# flyback.net
KiCad netlist of a schematic drawn in Altium Designer
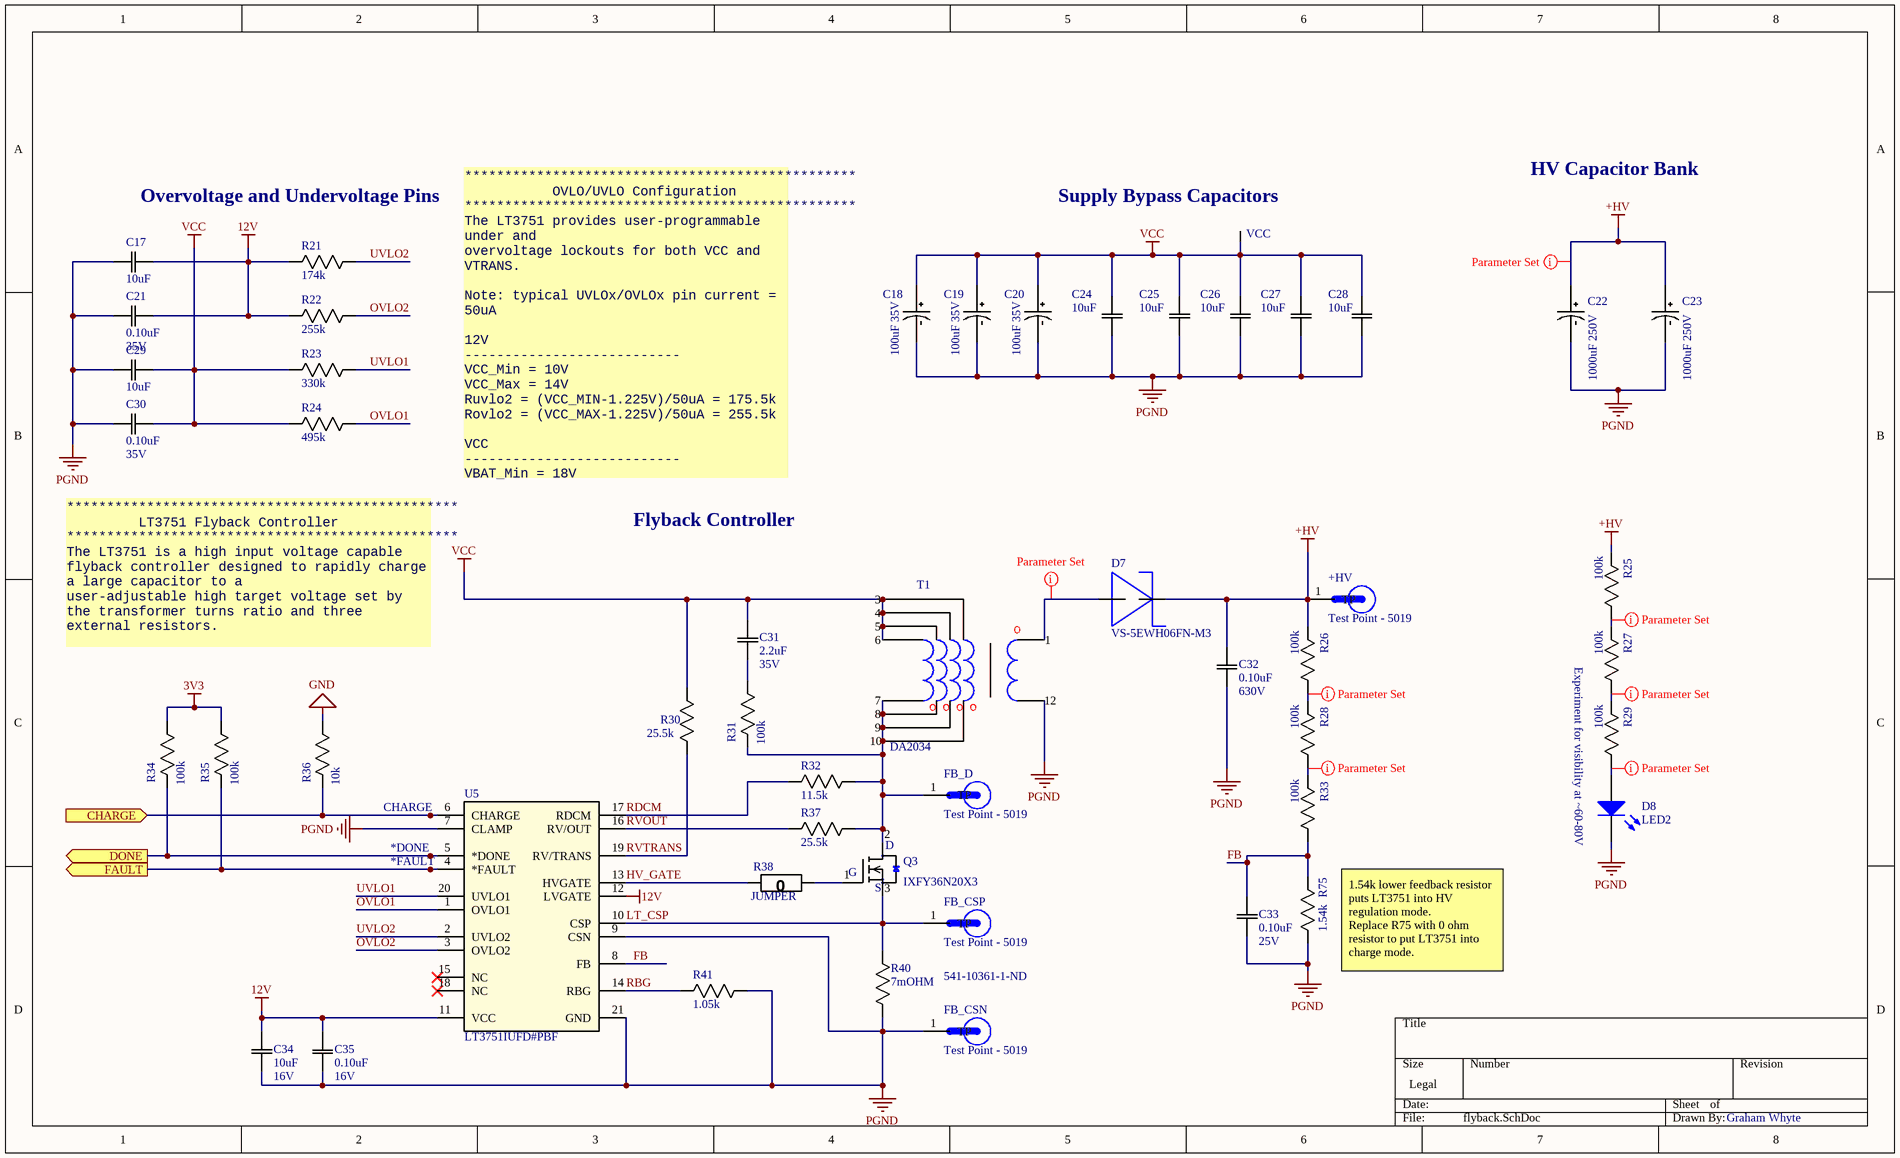
[diagram p0: flyback.SchDoc]

(export (version "E")
  (design (tool "Eeschema 10.0.6"))
  (components
    (comp (ref "*DONE")
      (value "Test Point (Via)")
      (footprint "TP")
      (libsource (lib "IC_Library") (part "Test Point (Via)"))
    )
    (comp (ref "*FAULT")
      (value "Test Point (Via)")
      (footprint "TP")
      (libsource (lib "IC_Library") (part "Test Point (Via)"))
    )
    (comp (ref "+HV")
      (value "Test Point - 5019")
      (footprint "TP380X203")
      (description "PC Test Point, Miniature Phosphor Bronze, Silver Plating Surface Mount Mounting Type")
      (fields (field (name "MP") "5019") (field (name "MF") "Keystone Electronics"))
      (libsource (lib "IC_Library") (part "Test Point - 5019"))
    )
    (comp (ref "C17")
      (value "10uF")
      (footprint "0805")
      (description "CAP CER 10UF 35V X7R 0805")
      (fields (field (name "TOLERANCE") "10%") (field (name "PART NUMBER") "CAP 10uF 35V"))
      (libsource (lib "capacitor_library") (part "CAP 10uF 35V"))
    )
    (comp (ref "C18")
      (value "100uF 35V")
      (footprint "CAP POL ALU 6.3x5.8")
      (description "CAP ALUM 100UF 35V SMD")
      (fields (field (name "TOLERANCE") "20%") (field (name "PART NUMBER") "CAP POL 100uF SMD"))
      (libsource (lib "capacitor_library") (part "CAP POL 100uF SMD"))
    )
    (comp (ref "C19")
      (value "100uF 35V")
      (footprint "CAP POL ALU 6.3x5.8")
      (description "CAP ALUM 100UF 35V SMD")
      (fields (field (name "TOLERANCE") "20%") (field (name "PART NUMBER") "CAP POL 100uF SMD"))
      (libsource (lib "capacitor_library") (part "CAP POL 100uF SMD"))
    )
    (comp (ref "C20")
      (value "100uF 35V")
      (footprint "CAP POL ALU 6.3x5.8")
      (description "CAP ALUM 100UF 35V SMD")
      (fields (field (name "TOLERANCE") "20%") (field (name "PART NUMBER") "CAP POL 100uF SMD"))
      (libsource (lib "capacitor_library") (part "CAP POL 100uF SMD"))
    )
    (comp (ref "C21")
      (value "0.10uF")
      (footprint "0805")
      (description "CAP CER 0.10UF 35V X7R 0805")
      (fields
        (field (name "TOLERANCE") "10%")
        (field (name "RATING") "35V")
        (field (name "PART NUMBER") "CAP 0.10uF 35V")
      )
      (libsource (lib "capacitor_library") (part "CAP 0.10uF 35V"))
    )
    (comp (ref "C22")
      (value "1000uF 250V")
      (footprint "RADIAL, CAN - THRU 25.4mm")
      (description "United Chemi-Con\r\nESMQ251VSN102MQ45S")
      (fields
        (field (name "MANUFACTURER") "United Chemi-Con")
        (field (name "MANUFACTURER PART NUMBER") "ESMQ251VSN102MQ45S")
      )
      (libsource (lib "capacitor_library") (part "CAP POL 1000uF"))
    )
    (comp (ref "C23")
      (value "1000uF 250V")
      (footprint "RADIAL, CAN - THRU 25.4mm")
      (description "United Chemi-Con\r\nESMQ251VSN102MQ45S")
      (fields
        (field (name "MANUFACTURER") "United Chemi-Con")
        (field (name "MANUFACTURER PART NUMBER") "ESMQ251VSN102MQ45S")
      )
      (libsource (lib "capacitor_library") (part "CAP POL 1000uF"))
    )
    (comp (ref "C24")
      (value "10uF")
      (footprint "0805")
      (description "CAP CER 10UF 35V X7R 0805")
      (fields (field (name "TOLERANCE") "10%") (field (name "PART NUMBER") "CAP 10uF 35V"))
      (libsource (lib "capacitor_library") (part "CAP 10uF 35V"))
    )
    (comp (ref "C25")
      (value "10uF")
      (footprint "0805")
      (description "CAP CER 10UF 35V X7R 0805")
      (fields (field (name "TOLERANCE") "10%") (field (name "PART NUMBER") "CAP 10uF 35V"))
      (libsource (lib "capacitor_library") (part "CAP 10uF 35V"))
    )
    (comp (ref "C26")
      (value "10uF")
      (footprint "0805")
      (description "CAP CER 10UF 35V X7R 0805")
      (fields (field (name "TOLERANCE") "10%") (field (name "PART NUMBER") "CAP 10uF 35V"))
      (libsource (lib "capacitor_library") (part "CAP 10uF 35V"))
    )
    (comp (ref "C27")
      (value "10uF")
      (footprint "0805")
      (description "CAP CER 10UF 35V X7R 0805")
      (fields (field (name "TOLERANCE") "10%") (field (name "PART NUMBER") "CAP 10uF 35V"))
      (libsource (lib "capacitor_library") (part "CAP 10uF 35V"))
    )
    (comp (ref "C28")
      (value "10uF")
      (footprint "0805")
      (description "CAP CER 10UF 35V X7R 0805")
      (fields (field (name "TOLERANCE") "10%") (field (name "PART NUMBER") "CAP 10uF 35V"))
      (libsource (lib "capacitor_library") (part "CAP 10uF 35V"))
    )
    (comp (ref "C29")
      (value "10uF")
      (footprint "0805")
      (description "CAP CER 10UF 35V X7R 0805")
      (fields (field (name "TOLERANCE") "10%") (field (name "PART NUMBER") "CAP 10uF 35V"))
      (libsource (lib "capacitor_library") (part "CAP 10uF 35V"))
    )
    (comp (ref "C30")
      (value "0.10uF")
      (footprint "0805")
      (description "CAP CER 0.10UF 35V X7R 0805")
      (fields
        (field (name "TOLERANCE") "10%")
        (field (name "RATING") "35V")
        (field (name "PART NUMBER") "CAP 0.10uF 35V")
      )
      (libsource (lib "capacitor_library") (part "CAP 0.10uF 35V"))
    )
    (comp (ref "C31")
      (value "2.2uF")
      (footprint "0603")
      (description "CAP CER 2.2UF 35V X7R 0603/0805")
      (fields
        (field (name "TOLERANCE") "10%")
        (field (name "RATING") "35V")
        (field (name "PART NUMBER") "CAP 2.2uF 35V")
      )
      (libsource (lib "capacitor_library") (part "CAP 2.2uF 35V"))
    )
    (comp (ref "C32")
      (value "0.10uF")
      (footprint "1210")
      (description "CAP CER 0.1uF 630V X7R 1210")
      (fields
        (field (name "TOLERANCE") "10%")
        (field (name "RATING") "630V")
        (field (name "PART NUMBER") "CAP 0.10uF 630V")
      )
      (libsource (lib "capacitor_library") (part "CAP 0.10uF 630V"))
    )
    (comp (ref "C33")
      (value "0.10uF")
      (footprint "0805")
      (description "CAP CER 0.10UF 25V X7R 0805")
      (fields
        (field (name "TOLERANCE") "10%")
        (field (name "RATING") "25V")
        (field (name "PART NUMBER") "CAP 0.10uF 25V")
      )
      (libsource (lib "capacitor_library") (part "CAP 0.10uF 25V"))
    )
    (comp (ref "C34")
      (value "10uF")
      (footprint "0603")
      (description "CAP CER 10UF 16V X5R 0603/0805")
      (fields
        (field (name "TOLERANCE") "10%")
        (field (name "RATING") "16V")
        (field (name "PART NUMBER") "CAP 10uF 16V")
      )
      (libsource (lib "capacitor_library") (part "CAP 10uF 16V"))
    )
    (comp (ref "C35")
      (value "0.10uF")
      (footprint "0603")
      (description "CAP CER 0.10UF 16V X5R 0603")
      (fields
        (field (name "TOLERANCE") "10%")
        (field (name "RATING") "16V")
        (field (name "PART NUMBER") "CAP 0.10uF 16V")
      )
      (libsource (lib "capacitor_library") (part "CAP 0.10uF 16V"))
    )
    (comp (ref "CHARGE")
      (value "Test Point (Via)")
      (footprint "TP")
      (libsource (lib "IC_Library") (part "Test Point (Via)"))
    )
    (comp (ref "D7")
      (value "VS-5EWH06FN-M3")
      (footprint "DPAK (TO-252)")
      (description "Diode Switching 600V 5A DPAK")
      (fields (field (name "MF") "Vishay Diodes"))
      (libsource (lib "Diode_Library") (part "VS-5EWH06FN-M3"))
    )
    (comp (ref "D8")
      (value "LED2")
      (footprint "3.2X1.6X1.1")
      (description "Typical RED, GREEN, YELLOW, AMBER GaAs LED")
      (fields (field (name "PART NUMBER") "LED GREEN SMD"))
      (libsource (lib "Diode_Library") (part "LED GREEN SMD"))
    )
    (comp (ref "FB_CSN")
      (value "Test Point - 5019")
      (footprint "TP380X203")
      (description "PC Test Point, Miniature Phosphor Bronze, Silver Plating Surface Mount Mounting Type")
      (fields (field (name "MP") "5019") (field (name "MF") "Keystone Electronics"))
      (libsource (lib "IC_Library") (part "Test Point - 5019"))
    )
    (comp (ref "FB_CSP")
      (value "Test Point - 5019")
      (footprint "TP380X203")
      (description "PC Test Point, Miniature Phosphor Bronze, Silver Plating Surface Mount Mounting Type")
      (fields (field (name "MP") "5019") (field (name "MF") "Keystone Electronics"))
      (libsource (lib "IC_Library") (part "Test Point - 5019"))
    )
    (comp (ref "FB_D")
      (value "Test Point - 5019")
      (footprint "TP380X203")
      (description "PC Test Point, Miniature Phosphor Bronze, Silver Plating Surface Mount Mounting Type")
      (fields (field (name "MP") "5019") (field (name "MF") "Keystone Electronics"))
      (libsource (lib "IC_Library") (part "Test Point - 5019"))
    )
    (comp (ref "Q3")
      (value "IXFY36N20X3")
      (footprint "DPAK (TO-252)")
      (description "N-Channel 200 V 36A (Tc) 176W (Tc) Surface Mount TO-252AA")
      (fields (field (name "PART NUMBER") "MOSFET N-CH IXFY36N20X3"))
      (libsource (lib "Transistor_Library") (part "MOSFET N-CH IXFY36N20X3"))
    )
    (comp (ref "R21")
      (value "174k")
      (footprint "0603")
      (description "RES SMD 174K OHM 1% 1/8W 0603")
      (fields
        (field (name "MANUFACTURER") "Yageo")
        (field (name "MANUFACTURER PART NUMBER") "RC0805FR-07174KL")
      )
      (libsource (lib "Resistor_Library") (part "RES 174k 1/8W"))
    )
    (comp (ref "R22")
      (value "255k")
      (footprint "0603")
      (description "RES 255k 1/8W - 1% 0603")
      (fields (field (name "PART NUMBER") "RES 255k 1/8W - 1%"))
      (libsource (lib "Resistor_Library") (part "RES 255k 1/8W - 1%"))
    )
    (comp (ref "R23")
      (value "330k")
      (footprint "0603")
      (description "RES SMD 274K OHM 1% 1/8W 0603")
      (fields (field (name "PART NUMBER") "RES 330k 1/8W - 1%"))
      (libsource (lib "Resistor_Library") (part "RES 330k 1/8W - 1%"))
    )
    (comp (ref "R24")
      (value "495k")
      (footprint "0603")
      (description "RES SMD 495K OHM 1% 1/8W 0603")
      (fields
        (field (name "MANUFACTURER") "Yageo")
        (field (name "MANUFACTURER PART NUMBER") "RC0805FR-07499KL")
      )
      (libsource (lib "Resistor_Library") (part "RES 495k 1/8W"))
    )
    (comp (ref "R25")
      (value "100k")
      (footprint "0603")
      (description "RES SMD 100K OHM 5% 1/8W 0603")
      (fields (field (name "TOLERANCE") "5%") (field (name "PART NUMBER") "RES 100k 1/8W - 5%"))
      (libsource (lib "") (part "RES 100k 1/8W 5%_1"))
    )
    (comp (ref "R26")
      (value "100k")
      (footprint "0603")
      (description "RES SMD 100K OHM 1% 1/8W 0603")
      (fields (field (name "TOLERANCE") "1%") (field (name "PART NUMBER") "RES 100k 1/8W - 1%"))
      (libsource (lib "") (part "RES 100k 1/8W 1%_1"))
    )
    (comp (ref "R27")
      (value "100k")
      (footprint "0603")
      (description "RES SMD 100K OHM 5% 1/8W 0603")
      (fields (field (name "TOLERANCE") "5%") (field (name "PART NUMBER") "RES 100k 1/8W - 5%"))
      (libsource (lib "Resistor_Library") (part "RES 100k 1/8W 5%"))
    )
    (comp (ref "R28")
      (value "100k")
      (footprint "0603")
      (description "RES SMD 100K OHM 1% 1/8W 0603")
      (fields (field (name "TOLERANCE") "1%") (field (name "PART NUMBER") "RES 100k 1/8W - 1%"))
      (libsource (lib "Resistor_Library") (part "RES 100k 1/8W 1%"))
    )
    (comp (ref "R29")
      (value "100k")
      (footprint "0603")
      (description "RES SMD 100K OHM 5% 1/8W 0603")
      (fields (field (name "TOLERANCE") "5%") (field (name "PART NUMBER") "RES 100k 1/8W - 5%"))
      (libsource (lib "Resistor_Library") (part "RES 100k 1/8W 5%"))
    )
    (comp (ref "R30")
      (value "25.5k")
      (footprint "0603")
      (description "RES SMD 25.5K OHM 0.1% 1/8W 0603")
      (fields
        (field (name "MANUFACTURER") "Panasonic")
        (field (name "MANUFACTURER PART NUMBER") "ERA-6AEB2552V")
      )
      (libsource (lib "Resistor_Library") (part "RES 25.5k 1/8W"))
    )
    (comp (ref "R31")
      (value "100k")
      (footprint "0603")
      (description "RES SMD 100K OHM 1% 1/8W 0603")
      (fields (field (name "TOLERANCE") "1%") (field (name "PART NUMBER") "RES 100k 1/8W - 1%"))
      (libsource (lib "") (part "RES 100k 1/8W 1%_1"))
    )
    (comp (ref "R32")
      (value "11.5k")
      (footprint "0603")
      (description "RES SMD 11.5K OHM 0.1% 1/8W 0603 Thin Film")
      (fields
        (field (name "MANUFACTURER") "Panasonic")
        (field (name "MANUFACTURER PART NUMBER") "ERA-6AEB1152V")
      )
      (libsource (lib "Resistor_Library") (part "RES 11.5k 1/8W"))
    )
    (comp (ref "R33")
      (value "100k")
      (footprint "0603")
      (description "RES SMD 100K OHM 1% 1/8W 0603")
      (fields (field (name "TOLERANCE") "1%") (field (name "PART NUMBER") "RES 100k 1/8W - 1%"))
      (libsource (lib "Resistor_Library") (part "RES 100k 1/8W 1%"))
    )
    (comp (ref "R34")
      (value "100k")
      (footprint "0603")
      (description "RES SMD 100K OHM 5% 1/8W 0603")
      (fields (field (name "TOLERANCE") "5%") (field (name "PART NUMBER") "RES 100k 1/8W - 5%"))
      (libsource (lib "Resistor_Library") (part "RES 100k 1/8W 5%"))
    )
    (comp (ref "R35")
      (value "100k")
      (footprint "0603")
      (description "RES SMD 100K OHM 5% 1/8W 0603")
      (fields (field (name "TOLERANCE") "5%") (field (name "PART NUMBER") "RES 100k 1/8W - 5%"))
      (libsource (lib "Resistor_Library") (part "RES 100k 1/8W 5%"))
    )
    (comp (ref "R36")
      (value "10k")
      (footprint "0603")
      (description "RES SMD 10K OHM 5% 1/8W 0603")
      (fields (field (name "TOLERANCE") "5%") (field (name "PART NUMBER") "RES 10k 1/8W - 5%"))
      (libsource (lib "Resistor_Library") (part "RES 10k 1/8W 5%"))
    )
    (comp (ref "R37")
      (value "25.5k")
      (footprint "0603")
      (description "RES SMD 25.5K OHM 0.1% 1/8W 0603")
      (fields
        (field (name "MANUFACTURER") "Panasonic")
        (field (name "MANUFACTURER PART NUMBER") "ERA-6AEB2552V")
      )
      (libsource (lib "Resistor_Library") (part "RES 25.5k 1/8W"))
    )
    (comp (ref "R38")
      (value "JUMPER")
      (footprint "0603")
      (description "RES SMD 0 OHM JUMPER GENERIC 0603")
      (fields (field (name "PART NUMBER") "RES 0 JUMPER"))
      (libsource (lib "Resistor_Library") (part "RES 0 JUMPER"))
    )
    (comp (ref "R40")
      (value "7mOHM")
      (footprint "2512")
      (description "RES SMD 7m OHM 1% 3W 2512")
      (fields
        (field (name "TOLERANCE") "1%")
        (field (name "MFG") "VISHAY")
        (field (name "SUPPLIER PART NUMBER 1") "541-10361-1-ND")
      )
      (libsource (lib "Resistor_Library") (part "RES 7m 3W"))
    )
    (comp (ref "R41")
      (value "1.05k")
      (footprint "0603")
      (description "RES SMD 1.05K OHM 0.1% 1/8W 0603")
      (fields (field (name "TOLERANCE") "0.1%") (field (name "PART NUMBER") "RES 1.05k 1/8W"))
      (libsource (lib "Resistor_Library") (part "RES 1.05k 1/8W"))
    )
    (comp (ref "R75")
      (value "1.54k")
      (footprint "0603")
      (description "RES SMD 1.54k OHM 1% 1/8W 0603")
      (fields (field (name "TOLERANCE") "1%") (field (name "PART NUMBER") "RES 1.54k 1_8W - 1%"))
      (libsource (lib "Resistor_Library") (part "RES 1.54k 1/8W - 1%"))
    )
    (comp (ref "T1")
      (value "DA2034")
      (footprint "DA2034")
      (description "Audio Transformers / Signal Transformers DA2032 Cap Chrgr For Linear LT3750/51")
      (libsource (lib "IC_Library") (part "DA2034"))
    )
    (comp (ref "U5")
      (value "LT3751IUFD#PBF")
      (footprint "QFN-20_UFD_LIT-M")
      (description "IC CTRLR CAP CHRGR 4.75V 20-QFN")
      (fields
        (field (name "MANUFACTURER_PART_NUMBER") "lt3751iufd#pbf")
        (field (name "COPYRIGHT") "Copyright (C) 2021 Ultra Librarian. All rights reserved.")
      )
      (libsource (lib "IC_Library") (part "LT3751IUFD#PBF"))
    )
    (comp (ref "VCC")
      (value "Test Point (Via)")
      (footprint "TP")
      (libsource (lib "IC_Library") (part "Test Point (Via)"))
    )
  )
  (nets
    (net (code "1") (name "+HV") (class "Default")
      (node (ref "+HV") (pin "1") (pinfunction "TP_1") (pintype "passive"))
      (node (ref "C22") (pin "POS") (pinfunction "POS_POS") (pintype "passive"))
      (node (ref "C23") (pin "POS") (pinfunction "POS_POS") (pintype "passive"))
      (node (ref "C32") (pin "1") (pinfunction "C1_1") (pintype "passive"))
      (node (ref "D7") (pin "OUT") (pinfunction "OUT_OUT") (pintype "passive"))
      (node (ref "R25") (pin "2") (pinfunction "R2_2") (pintype "passive"))
      (node (ref "R26") (pin "2") (pinfunction "R2_2") (pintype "passive"))
    )
    (net (code "3") (name "/CHARGE") (class "Default")
      (node (ref "CHARGE") (pin "1") (pinfunction "1_1") (pintype "passive"))
      (node (ref "R36") (pin "2") (pinfunction "R2_2") (pintype "passive"))
      (node (ref "U5") (pin "6") (pinfunction "CHARGE_6") (pintype "passive"))
    )
    (net (code "4") (name "/DONE") (class "Default")
      (node (ref "*DONE") (pin "1") (pinfunction "1_1") (pintype "passive"))
      (node (ref "R34") (pin "2") (pinfunction "R2_2") (pintype "passive"))
      (node (ref "U5") (pin "5") (pinfunction "*DONE_5") (pintype "passive"))
    )
    (net (code "5") (name "/FAULT") (class "Default")
      (node (ref "*FAULT") (pin "1") (pinfunction "1_1") (pintype "passive"))
      (node (ref "R35") (pin "2") (pinfunction "R2_2") (pintype "passive"))
      (node (ref "U5") (pin "4") (pinfunction "*FAULT_4") (pintype "passive"))
    )
    (net (code "6") (name "/FB") (class "Default")
      (node (ref "C33") (pin "1") (pinfunction "C1_1") (pintype "passive"))
      (node (ref "R33") (pin "1") (pinfunction "R1_1") (pintype "passive"))
      (node (ref "R75") (pin "2") (pinfunction "R2_2") (pintype "passive"))
      (node (ref "U5") (pin "8") (pinfunction "FB_8") (pintype "passive"))
    )
    (net (code "7") (name "/HV_GATE") (class "Default")
      (node (ref "R38") (pin "2") (pinfunction "R2_2") (pintype "passive"))
      (node (ref "U5") (pin "13") (pinfunction "HVGATE_13") (pintype "passive"))
    )
    (net (code "8") (name "/LT_CSP") (class "Default")
      (node (ref "FB_CSP") (pin "1") (pinfunction "TP_1") (pintype "passive"))
      (node (ref "Q3") (pin "3") (pinfunction "S_3") (pintype "passive"))
      (node (ref "R40") (pin "2") (pinfunction "R2_2") (pintype "passive"))
      (node (ref "U5") (pin "10") (pinfunction "CSP_10") (pintype "passive"))
    )
    (net (code "9") (name "/OVLO1") (class "Default")
      (node (ref "R24") (pin "1") (pinfunction "R1_1") (pintype "passive"))
      (node (ref "U5") (pin "1") (pinfunction "OVLO1_1") (pintype "passive"))
    )
    (net (code "10") (name "/OVLO2") (class "Default")
      (node (ref "R22") (pin "1") (pinfunction "R1_1") (pintype "passive"))
      (node (ref "U5") (pin "3") (pinfunction "OVLO2_3") (pintype "passive"))
    )
    (net (code "11") (name "/RBG") (class "Default")
      (node (ref "R41") (pin "2") (pinfunction "R2_2") (pintype "passive"))
      (node (ref "U5") (pin "14") (pinfunction "RBG_14") (pintype "passive"))
    )
    (net (code "12") (name "/RDCM") (class "Default")
      (node (ref "R32") (pin "2") (pinfunction "R2_2") (pintype "passive"))
      (node (ref "U5") (pin "17") (pinfunction "RDCM_17") (pintype "passive"))
    )
    (net (code "13") (name "/RVOUT") (class "Default")
      (node (ref "R37") (pin "2") (pinfunction "R2_2") (pintype "passive"))
      (node (ref "U5") (pin "16") (pinfunction "RV/OUT_16") (pintype "passive"))
    )
    (net (code "14") (name "/RVTRANS") (class "Default")
      (node (ref "R30") (pin "2") (pinfunction "R2_2") (pintype "passive"))
      (node (ref "U5") (pin "19") (pinfunction "RV/TRANS_19") (pintype "passive"))
    )
    (net (code "15") (name "/UVLO1") (class "Default")
      (node (ref "R23") (pin "1") (pinfunction "R1_1") (pintype "passive"))
      (node (ref "U5") (pin "20") (pinfunction "UVLO1_20") (pintype "passive"))
    )
    (net (code "16") (name "/UVLO2") (class "Default")
      (node (ref "R21") (pin "1") (pinfunction "R1_1") (pintype "passive"))
      (node (ref "U5") (pin "2") (pinfunction "UVLO2_2") (pintype "passive"))
    )
    (net (code "17") (name "3V3") (class "Default")
      (node (ref "R34") (pin "1") (pinfunction "R1_1") (pintype "passive"))
      (node (ref "R35") (pin "1") (pinfunction "R1_1") (pintype "passive"))
    )
    (net (code "18") (name "12V") (class "Default")
      (node (ref "C17") (pin "2") (pinfunction "C2_2") (pintype "passive"))
      (node (ref "C21") (pin "2") (pinfunction "C2_2") (pintype "passive"))
      (node (ref "C34") (pin "1") (pinfunction "C1_1") (pintype "passive"))
      (node (ref "C35") (pin "2") (pinfunction "C2_2") (pintype "passive"))
      (node (ref "R21") (pin "2") (pinfunction "R2_2") (pintype "passive"))
      (node (ref "R22") (pin "2") (pinfunction "R2_2") (pintype "passive"))
      (node (ref "U5") (pin "11") (pinfunction "VCC_11") (pintype "power_in"))
      (node (ref "U5") (pin "12") (pinfunction "LVGATE_12") (pintype "passive"))
    )
    (net (code "19") (name "GND") (class "Default")
      (node (ref "R36") (pin "1") (pinfunction "R1_1") (pintype "passive"))
    )
    (net (code "20") (name "Net-(C31-C1)") (class "Default")
      (node (ref "C31") (pin "1") (pinfunction "C1_1") (pintype "passive"))
      (node (ref "R31") (pin "1") (pinfunction "R1_1") (pintype "passive"))
    )
    (net (code "21") (name "Net-(D7-PadIN)") (class "Default")
      (node (ref "D7") (pin "IN") (pinfunction "IN_IN") (pintype "passive"))
      (node (ref "T1") (pin "1") (pinfunction "1_1") (pintype "passive"))
    )
    (net (code "22") (name "Net-(D8-A)") (class "Default")
      (node (ref "D8") (pin "1") (pinfunction "A_1") (pintype "passive"))
      (node (ref "R29") (pin "1") (pinfunction "R1_1") (pintype "passive"))
    )
    (net (code "23") (name "Net-(FB_D-TP)") (class "Default")
      (node (ref "FB_D") (pin "1") (pinfunction "TP_1") (pintype "passive"))
      (node (ref "Q3") (pin "2") (pinfunction "D_2") (pintype "passive"))
      (node (ref "R31") (pin "2") (pinfunction "R2_2") (pintype "passive"))
      (node (ref "R32") (pin "1") (pinfunction "R1_1") (pintype "passive"))
      (node (ref "R37") (pin "1") (pinfunction "R1_1") (pintype "passive"))
      (node (ref "T1") (pin "10") (pinfunction "10_10") (pintype "passive"))
      (node (ref "T1") (pin "7") (pinfunction "7_7") (pintype "passive"))
      (node (ref "T1") (pin "8") (pinfunction "8_8") (pintype "passive"))
      (node (ref "T1") (pin "9") (pinfunction "9_9") (pintype "passive"))
    )
    (net (code "24") (name "Net-(Q3-G)") (class "Default")
      (node (ref "Q3") (pin "1") (pinfunction "G_1") (pintype "passive"))
      (node (ref "R38") (pin "1") (pinfunction "R1_1") (pintype "passive"))
    )
    (net (code "25") (name "Net-(R25-R1)") (class "Default")
      (node (ref "R25") (pin "1") (pinfunction "R1_1") (pintype "passive"))
      (node (ref "R27") (pin "2") (pinfunction "R2_2") (pintype "passive"))
    )
    (net (code "26") (name "Net-(R26-R1)") (class "Default")
      (node (ref "R26") (pin "1") (pinfunction "R1_1") (pintype "passive"))
      (node (ref "R28") (pin "2") (pinfunction "R2_2") (pintype "passive"))
    )
    (net (code "27") (name "Net-(R27-R1)") (class "Default")
      (node (ref "R27") (pin "1") (pinfunction "R1_1") (pintype "passive"))
      (node (ref "R29") (pin "2") (pinfunction "R2_2") (pintype "passive"))
    )
    (net (code "28") (name "Net-(R28-R1)") (class "Default")
      (node (ref "R28") (pin "1") (pinfunction "R1_1") (pintype "passive"))
      (node (ref "R33") (pin "2") (pinfunction "R2_2") (pintype "passive"))
    )
    (net (code "29") (name "PGND") (class "Default")
      (node (ref "C17") (pin "1") (pinfunction "C1_1") (pintype "passive"))
      (node (ref "C18") (pin "NEG") (pinfunction "NEG_NEG") (pintype "passive"))
      (node (ref "C19") (pin "NEG") (pinfunction "NEG_NEG") (pintype "passive"))
      (node (ref "C20") (pin "NEG") (pinfunction "NEG_NEG") (pintype "passive"))
      (node (ref "C21") (pin "1") (pinfunction "C1_1") (pintype "passive"))
      (node (ref "C22") (pin "NEG") (pinfunction "NEG_NEG") (pintype "passive"))
      (node (ref "C23") (pin "NEG") (pinfunction "NEG_NEG") (pintype "passive"))
      (node (ref "C24") (pin "1") (pinfunction "C1_1") (pintype "passive"))
      (node (ref "C25") (pin "1") (pinfunction "C1_1") (pintype "passive"))
      (node (ref "C26") (pin "1") (pinfunction "C1_1") (pintype "passive"))
      (node (ref "C27") (pin "1") (pinfunction "C1_1") (pintype "passive"))
      (node (ref "C28") (pin "1") (pinfunction "C1_1") (pintype "passive"))
      (node (ref "C29") (pin "1") (pinfunction "C1_1") (pintype "passive"))
      (node (ref "C30") (pin "1") (pinfunction "C1_1") (pintype "passive"))
      (node (ref "C32") (pin "2") (pinfunction "C2_2") (pintype "passive"))
      (node (ref "C33") (pin "2") (pinfunction "C2_2") (pintype "passive"))
      (node (ref "C34") (pin "2") (pinfunction "C2_2") (pintype "passive"))
      (node (ref "C35") (pin "1") (pinfunction "C1_1") (pintype "passive"))
      (node (ref "D8") (pin "2") (pinfunction "K_2") (pintype "passive"))
      (node (ref "FB_CSN") (pin "1") (pinfunction "TP_1") (pintype "passive"))
      (node (ref "R40") (pin "1") (pinfunction "R1_1") (pintype "passive"))
      (node (ref "R41") (pin "1") (pinfunction "R1_1") (pintype "passive"))
      (node (ref "R75") (pin "1") (pinfunction "R1_1") (pintype "passive"))
      (node (ref "T1") (pin "12") (pinfunction "12_12") (pintype "passive"))
      (node (ref "U5") (pin "21") (pinfunction "GND_21") (pintype "passive"))
      (node (ref "U5") (pin "7") (pinfunction "CLAMP_7") (pintype "passive"))
      (node (ref "U5") (pin "9") (pinfunction "CSN_9") (pintype "passive"))
    )
    (net (code "30") (name "VCC") (class "Default")
      (node (ref "C18") (pin "POS") (pinfunction "POS_POS") (pintype "passive"))
      (node (ref "C19") (pin "POS") (pinfunction "POS_POS") (pintype "passive"))
      (node (ref "C20") (pin "POS") (pinfunction "POS_POS") (pintype "passive"))
      (node (ref "C24") (pin "2") (pinfunction "C2_2") (pintype "passive"))
      (node (ref "C25") (pin "2") (pinfunction "C2_2") (pintype "passive"))
      (node (ref "C26") (pin "2") (pinfunction "C2_2") (pintype "passive"))
      (node (ref "C27") (pin "2") (pinfunction "C2_2") (pintype "passive"))
      (node (ref "C28") (pin "2") (pinfunction "C2_2") (pintype "passive"))
      (node (ref "C29") (pin "2") (pinfunction "C2_2") (pintype "passive"))
      (node (ref "C30") (pin "2") (pinfunction "C2_2") (pintype "passive"))
      (node (ref "C31") (pin "2") (pinfunction "C2_2") (pintype "passive"))
      (node (ref "R23") (pin "2") (pinfunction "R2_2") (pintype "passive"))
      (node (ref "R24") (pin "2") (pinfunction "R2_2") (pintype "passive"))
      (node (ref "R30") (pin "1") (pinfunction "R1_1") (pintype "passive"))
      (node (ref "T1") (pin "3") (pinfunction "3_3") (pintype "passive"))
      (node (ref "T1") (pin "4") (pinfunction "4_4") (pintype "passive"))
      (node (ref "T1") (pin "5") (pinfunction "5_5") (pintype "passive"))
      (node (ref "T1") (pin "6") (pinfunction "6_6") (pintype "passive"))
      (node (ref "VCC") (pin "1") (pinfunction "1_1") (pintype "passive"))
    )
    (net (code "31") (name "unconnected-(U5-NC-Pad15)") (class "Default")
      (node (ref "U5") (pin "15") (pinfunction "NC_15") (pintype "passive+no_connect"))
    )
    (net (code "32") (name "unconnected-(U5-NC-Pad18)") (class "Default")
      (node (ref "U5") (pin "18") (pinfunction "NC_18") (pintype "passive+no_connect"))
    )
  )
)
